# PA93_PCBSCH.net
KiCad netlist of a schematic drawn in Altium Designer
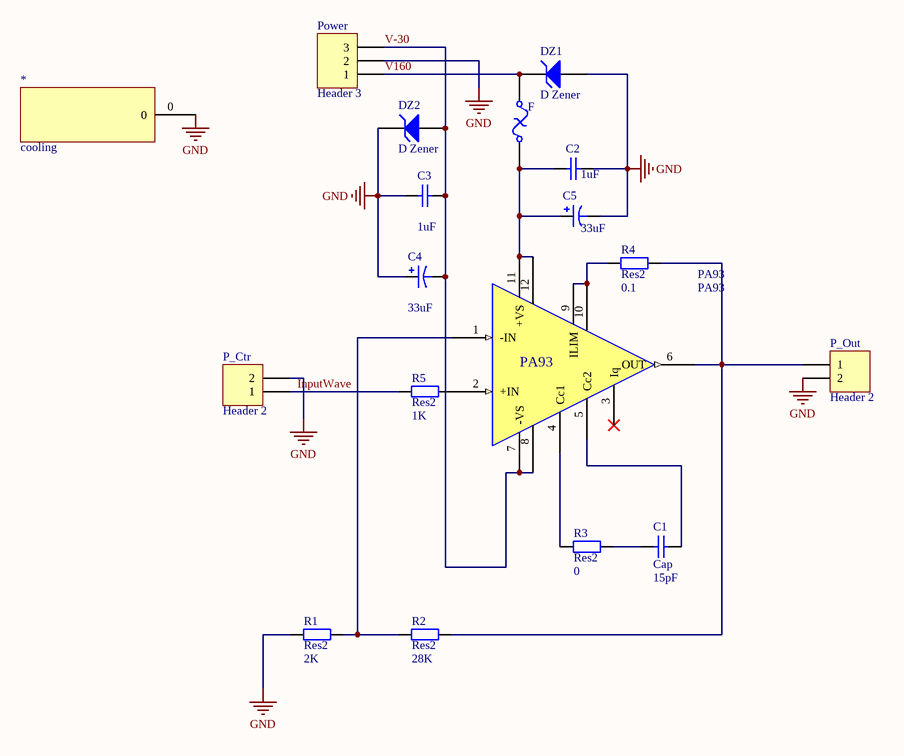
[diagram p0: PA93_PCBSCH.SchDoc]

(export (version "E")
  (design (tool "Eeschema 10.0.6"))
  (components
    (comp (ref "*") (value "cooling") (footprint "cooling") (libsource (lib "PA93") (part "cooling")))
    (comp (ref "C1")
      (value "Cap")
      (footprint "1206")
      (description "Capacitor")
      (fields (field (name "ALTIUM_VALUE") "15pF") (field (name "PUBLISHER") "Altium Limited"))
      (libsource (lib "Miscellaneous Devices") (part "Cap"))
    )
    (comp (ref "C2")
      (value "1uF")
      (footprint "1812")
      (description "Capacitor")
      (fields (field (name "Comment") "Cap") (field (name "PUBLISHER") "Altium Limited"))
      (libsource (lib "Miscellaneous Devices") (part "Cap"))
    )
    (comp (ref "C3")
      (value "1uF")
      (footprint "1812")
      (description "Capacitor")
      (fields (field (name "Comment") "Cap") (field (name "PUBLISHER") "Altium Limited"))
      (libsource (lib "Miscellaneous Devices") (part "Cap"))
    )
    (comp (ref "C4")
      (value "33uF")
      (footprint "RB7.6-15")
      (description "Polarized Capacitor (Radial)")
      (fields (field (name "Comment") "Cap Pol1") (field (name "PUBLISHER") "Altium Limited"))
      (libsource (lib "Miscellaneous Devices") (part "Cap Pol1"))
    )
    (comp (ref "C5")
      (value "33uF")
      (footprint "RB7.6-15")
      (description "Polarized Capacitor (Radial)")
      (fields (field (name "Comment") "Cap Pol1") (field (name "PUBLISHER") "Altium Limited"))
      (libsource (lib "Miscellaneous Devices") (part "Cap Pol1"))
    )
    (comp (ref "DZ1")
      (value "D Zener")
      (footprint "DO-15")
      (description "Zener Diode")
      (fields (field (name "PUBLISHER") "Altium Limited"))
      (libsource (lib "Miscellaneous Devices") (part "D Zener"))
    )
    (comp (ref "DZ2")
      (value "D Zener")
      (footprint "DO-15")
      (description "Zener Diode")
      (fields (field (name "PUBLISHER") "Altium Limited"))
      (libsource (lib "Miscellaneous Devices") (part "D Zener"))
    )
    (comp (ref "F")
      (value "Fuse Thermal")
      (footprint "PIN-W2/E2.8")
      (description "Thermal Fuse")
      (fields (field (name "PUBLISHER") "Altium Limited"))
      (libsource (lib "Miscellaneous Devices") (part "Fuse Thermal"))
    )
    (comp (ref "PA93") (value "PA93") (footprint "HDR1X12") (libsource (lib "PA93") (part "PA93")))
    (comp (ref "Power")
      (value "Header 3")
      (footprint "jk128-500-3p")
      (description "Header, 3-Pin")
      (fields (field (name "PUBLISHER") "Altium Limited"))
      (libsource (lib "Miscellaneous Connectors") (part "Header 3"))
    )
    (comp (ref "P_Ctr")
      (value "Header 2")
      (footprint "JK128-500-2p")
      (description "Header, 2-Pin")
      (fields (field (name "PUBLISHER") "Altium Limited"))
      (libsource (lib "") (part "Header 2_1"))
    )
    (comp (ref "P_Out")
      (value "Header 2")
      (footprint "jk128-500-2p")
      (description "Header, 2-Pin")
      (fields (field (name "PUBLISHER") "Altium Limited"))
      (libsource (lib "Miscellaneous Connectors") (part "Header 2"))
    )
    (comp (ref "R1")
      (value "Res2")
      (footprint "AXIAL-0.15")
      (description "Resistor")
      (fields (field (name "ALTIUM_VALUE") "2K") (field (name "PUBLISHER") "Altium Limited"))
      (libsource (lib "Miscellaneous Devices") (part "Res2"))
    )
    (comp (ref "R2")
      (value "Res2")
      (footprint "AXIAL-0.15")
      (description "Resistor")
      (fields (field (name "ALTIUM_VALUE") "28K") (field (name "PUBLISHER") "Altium Limited"))
      (libsource (lib "Miscellaneous Devices") (part "Res2"))
    )
    (comp (ref "R3")
      (value "Res2")
      (footprint "1206")
      (description "Resistor")
      (fields (field (name "ALTIUM_VALUE") "0") (field (name "PUBLISHER") "Altium Limited"))
      (libsource (lib "Miscellaneous Devices") (part "Res2"))
    )
    (comp (ref "R4")
      (value "Res2")
      (footprint "axial0.4")
      (description "Resistor")
      (fields (field (name "ALTIUM_VALUE") "0.1") (field (name "PUBLISHER") "Altium Limited"))
      (libsource (lib "Miscellaneous Devices") (part "Res2"))
    )
    (comp (ref "R5")
      (value "Res2")
      (footprint "AXIAL-0.15")
      (description "Resistor")
      (fields (field (name "ALTIUM_VALUE") "1K") (field (name "PUBLISHER") "Altium Limited"))
      (libsource (lib "Miscellaneous Devices") (part "Res2"))
    )
  )
  (nets
    (net (code "1") (name "/InputWave") (class "Default")
      (node (ref "P_Ctr") (pin "1") (pinfunction "1_1") (pintype "passive"))
      (node (ref "R5") (pin "1") (pinfunction "1_1") (pintype "passive"))
    )
    (net (code "2") (name "/V-30") (class "Default")
      (node (ref "C3") (pin "2") (pinfunction "2_2") (pintype "passive"))
      (node (ref "C4") (pin "2") (pinfunction "2_2") (pintype "passive"))
      (node (ref "DZ2") (pin "1") (pinfunction "A_1") (pintype "passive"))
      (node (ref "PA93") (pin "7") (pinfunction "-VS_7") (pintype "passive"))
      (node (ref "PA93") (pin "8") (pinfunction "-VS_8") (pintype "passive"))
      (node (ref "Power") (pin "3") (pinfunction "3_3") (pintype "passive"))
    )
    (net (code "3") (name "/V160") (class "Default")
      (node (ref "DZ1") (pin "2") (pinfunction "K_2") (pintype "passive"))
      (node (ref "F") (pin "2") (pinfunction "2_2") (pintype "passive"))
      (node (ref "Power") (pin "1") (pinfunction "1_1") (pintype "passive"))
    )
    (net (code "4") (name "GND") (class "Default")
      (node (ref "*") (pin "0") (pinfunction "0_0") (pintype "passive"))
      (node (ref "C2") (pin "2") (pinfunction "2_2") (pintype "passive"))
      (node (ref "C3") (pin "1") (pinfunction "1_1") (pintype "passive"))
      (node (ref "C4") (pin "1") (pinfunction "1_1") (pintype "passive"))
      (node (ref "C5") (pin "2") (pinfunction "2_2") (pintype "passive"))
      (node (ref "DZ1") (pin "1") (pinfunction "A_1") (pintype "passive"))
      (node (ref "DZ2") (pin "2") (pinfunction "K_2") (pintype "passive"))
      (node (ref "P_Ctr") (pin "2") (pinfunction "2_2") (pintype "passive"))
      (node (ref "P_Out") (pin "2") (pinfunction "2_2") (pintype "passive"))
      (node (ref "Power") (pin "2") (pinfunction "2_2") (pintype "passive"))
      (node (ref "R1") (pin "1") (pinfunction "1_1") (pintype "passive"))
    )
    (net (code "5") (name "Net-(C1-Pad1)") (class "Default")
      (node (ref "C1") (pin "1") (pinfunction "1_1") (pintype "passive"))
      (node (ref "R3") (pin "2") (pinfunction "2_2") (pintype "passive"))
    )
    (net (code "6") (name "Net-(C2-Pad1)") (class "Default")
      (node (ref "C2") (pin "1") (pinfunction "1_1") (pintype "passive"))
      (node (ref "C5") (pin "1") (pinfunction "1_1") (pintype "passive"))
      (node (ref "F") (pin "1") (pinfunction "1_1") (pintype "passive"))
      (node (ref "PA93") (pin "11") (pinfunction "+VS_11") (pintype "passive"))
      (node (ref "PA93") (pin "12") (pinfunction "+VS_12") (pintype "passive"))
    )
    (net (code "7") (name "Net-(PA93-+IN)") (class "Default")
      (node (ref "PA93") (pin "2") (pinfunction "+IN_2") (pintype "input"))
      (node (ref "R5") (pin "2") (pinfunction "2_2") (pintype "passive"))
    )
    (net (code "8") (name "Net-(PA93--IN)") (class "Default")
      (node (ref "PA93") (pin "1") (pinfunction "-IN_1") (pintype "input"))
      (node (ref "R1") (pin "2") (pinfunction "2_2") (pintype "passive"))
      (node (ref "R2") (pin "1") (pinfunction "1_1") (pintype "passive"))
    )
    (net (code "9") (name "Net-(PA93-Cc1)") (class "Default")
      (node (ref "PA93") (pin "4") (pinfunction "Cc1_4") (pintype "passive"))
      (node (ref "R3") (pin "1") (pinfunction "1_1") (pintype "passive"))
    )
    (net (code "10") (name "Net-(PA93-Cc2)") (class "Default")
      (node (ref "C1") (pin "2") (pinfunction "2_2") (pintype "passive"))
      (node (ref "PA93") (pin "5") (pinfunction "Cc2_5") (pintype "passive"))
    )
    (net (code "11") (name "Net-(PA93-ILIM-Pad10)") (class "Default")
      (node (ref "PA93") (pin "10") (pinfunction "ILIM_10") (pintype "passive"))
      (node (ref "PA93") (pin "9") (pinfunction "ILIM_9") (pintype "passive"))
      (node (ref "R4") (pin "1") (pinfunction "1_1") (pintype "passive"))
    )
    (net (code "12") (name "Net-(PA93-OUT)") (class "Default")
      (node (ref "PA93") (pin "6") (pinfunction "OUT_6") (pintype "output"))
      (node (ref "P_Out") (pin "1") (pinfunction "1_1") (pintype "passive"))
      (node (ref "R2") (pin "2") (pinfunction "2_2") (pintype "passive"))
      (node (ref "R4") (pin "2") (pinfunction "2_2") (pintype "passive"))
    )
    (net (code "13") (name "unconnected-(PA93-Iq-Pad3)") (class "Default")
      (node (ref "PA93") (pin "3") (pinfunction "Iq_3") (pintype "passive+no_connect"))
    )
  )
)
